# gnublin_ext_ssd1963.net
KiCad netlist of a schematic drawn in EAGLE
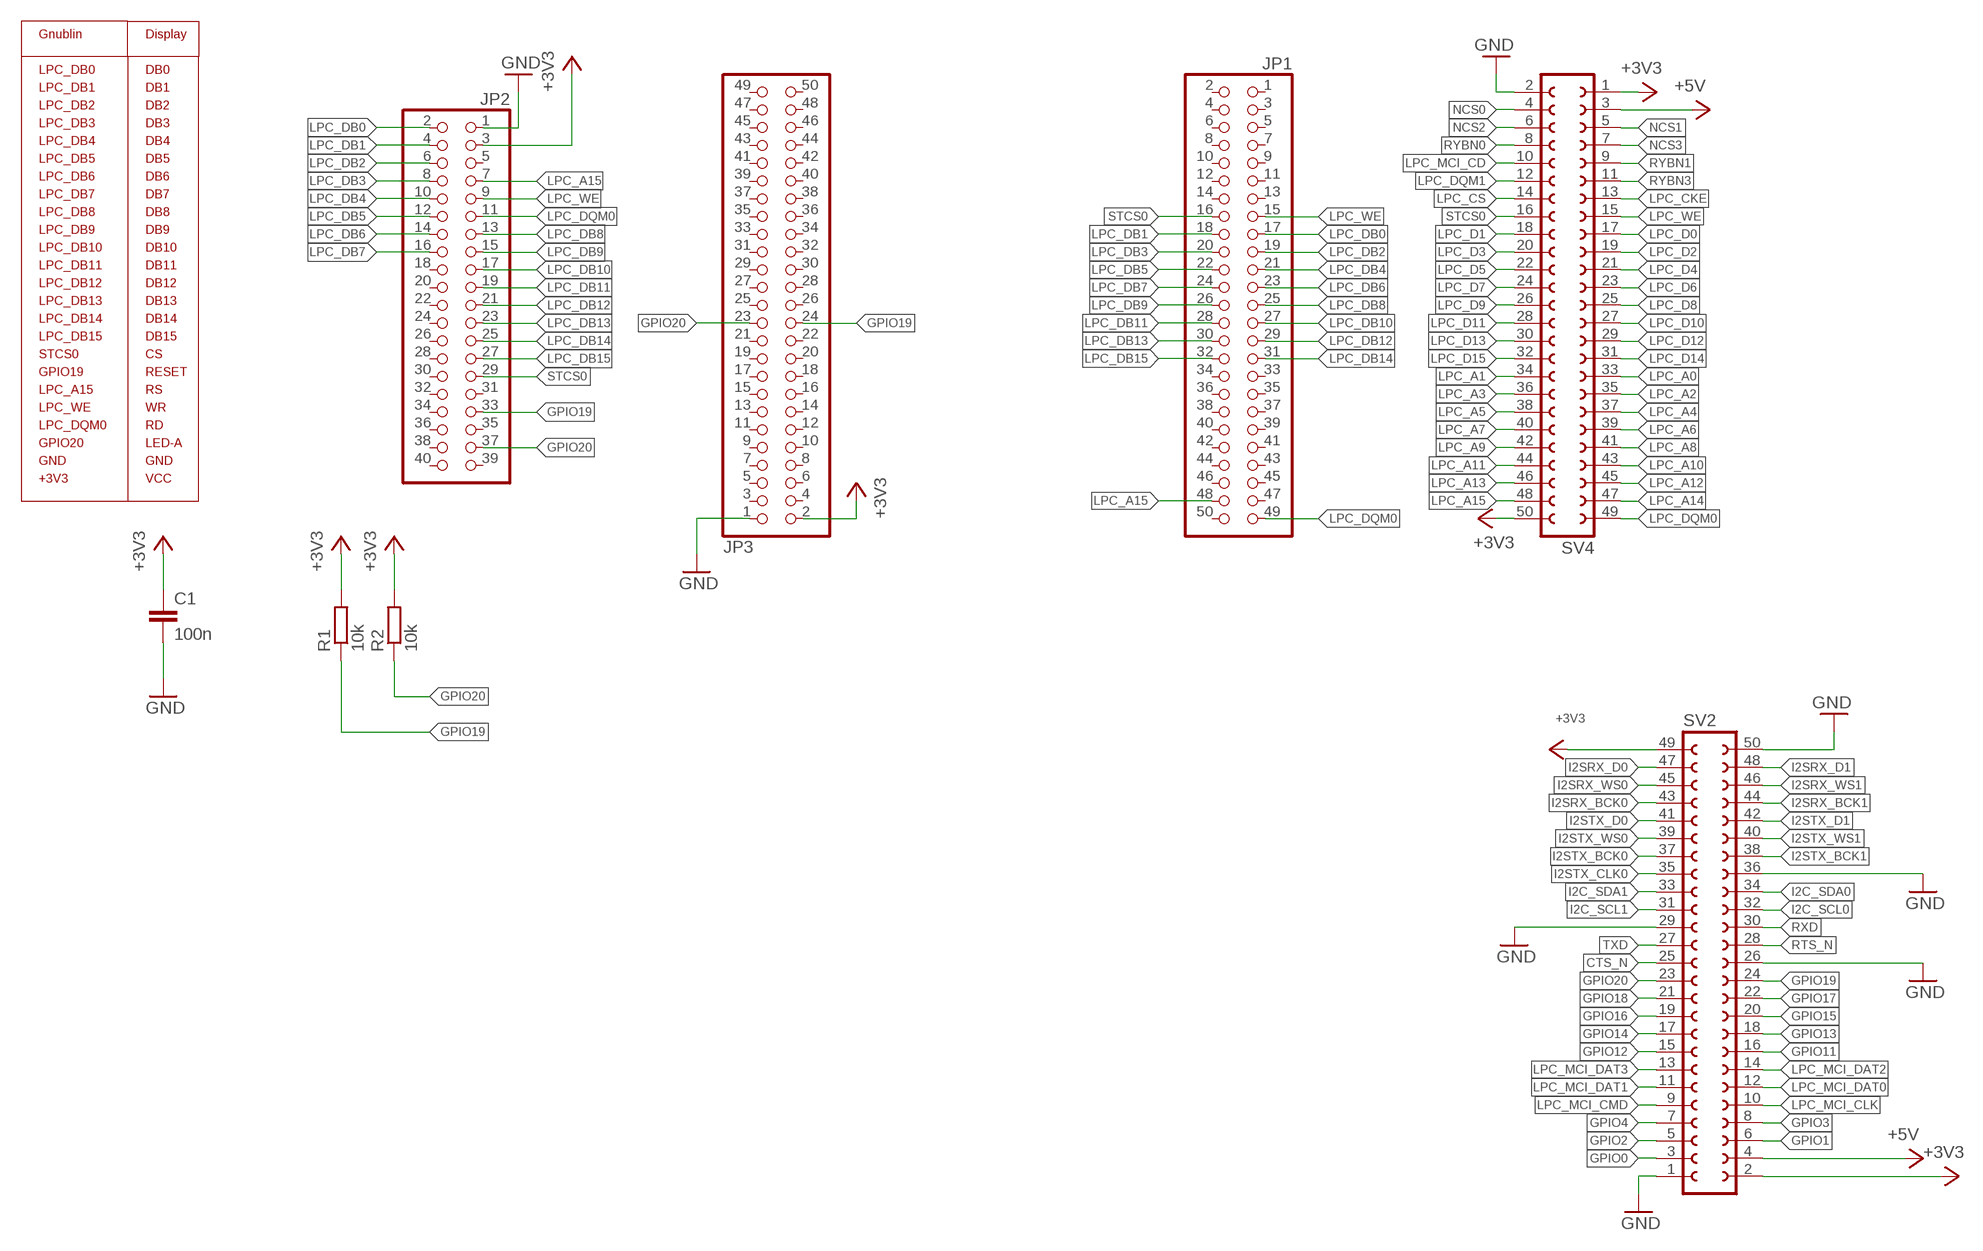
[diagram p0: schematic, sheet 1]

(export (version "E")
  (design (tool "Eeschema 10.0.6"))
  (components
    (comp (ref "C1")
      (value "100n")
      (footprint "eagle-import:C0805")
      (libsource (lib "eagle-import") (part "C-EUC0805"))
    )
    (comp (ref "JP1")
      (value "PINHD-2X25_2.54-SMD")
      (footprint "eagle-import:2X25SMD")
      (libsource (lib "eagle-import") (part "PINHD-2X25_2.54-SMD"))
    )
    (comp (ref "JP2")
      (value "PINHD-2X20")
      (footprint "eagle-import:2X20")
      (libsource (lib "eagle-import") (part "PINHD-2X20"))
    )
    (comp (ref "JP3")
      (value "PINHD-2X25_2.54-SMD")
      (footprint "eagle-import:2X25SMD")
      (libsource (lib "eagle-import") (part "PINHD-2X25_2.54-SMD"))
    )
    (comp (ref "R1")
      (value "10k")
      (footprint "eagle-import:R0603")
      (libsource (lib "eagle-import") (part "R-EU_R0603"))
    )
    (comp (ref "R2")
      (value "10k")
      (footprint "eagle-import:R0603")
      (libsource (lib "eagle-import") (part "R-EU_R0603"))
    )
    (comp (ref "SV2")
      (value "FE25-2")
      (footprint "eagle-import:FE25-2")
      (libsource (lib "eagle-import") (part "FE25-2"))
    )
    (comp (ref "SV4")
      (value "FE25-2")
      (footprint "eagle-import:FE25-2")
      (libsource (lib "eagle-import") (part "FE25-2"))
    )
  )
  (nets
    (net (code "1") (name "+3V3") (class "Default")
      (node (ref "C1") (pin "1") (pinfunction "1_1") (pintype "passive"))
      (node (ref "JP2") (pin "3") (pinfunction "3_3") (pintype "passive"))
      (node (ref "JP3") (pin "2") (pinfunction "2_2") (pintype "passive"))
      (node (ref "R1") (pin "2") (pinfunction "2_2") (pintype "passive"))
      (node (ref "R2") (pin "2") (pinfunction "2_2") (pintype "passive"))
      (node (ref "SV2") (pin "2") (pinfunction "2_2") (pintype "passive"))
      (node (ref "SV2") (pin "49") (pinfunction "49_49") (pintype "passive"))
      (node (ref "SV4") (pin "1") (pinfunction "1_1") (pintype "passive"))
      (node (ref "SV4") (pin "50") (pinfunction "50_50") (pintype "passive"))
    )
    (net (code "2") (name "+5V") (class "Default")
      (node (ref "SV2") (pin "4") (pinfunction "4_4") (pintype "passive"))
      (node (ref "SV4") (pin "3") (pinfunction "3_3") (pintype "passive"))
    )
    (net (code "3") (name "CTS_N") (class "Default")
      (node (ref "SV2") (pin "25") (pinfunction "25_25") (pintype "passive"))
    )
    (net (code "4") (name "GND") (class "Default")
      (node (ref "C1") (pin "2") (pinfunction "2_2") (pintype "passive"))
      (node (ref "JP2") (pin "1") (pinfunction "1_1") (pintype "passive"))
      (node (ref "JP3") (pin "1") (pinfunction "1_1") (pintype "passive"))
      (node (ref "SV2") (pin "1") (pinfunction "1_1") (pintype "passive"))
      (node (ref "SV2") (pin "26") (pinfunction "26_26") (pintype "passive"))
      (node (ref "SV2") (pin "29") (pinfunction "29_29") (pintype "passive"))
      (node (ref "SV2") (pin "36") (pinfunction "36_36") (pintype "passive"))
      (node (ref "SV2") (pin "50") (pinfunction "50_50") (pintype "passive"))
      (node (ref "SV4") (pin "2") (pinfunction "2_2") (pintype "passive"))
    )
    (net (code "5") (name "GPIO0") (class "Default")
      (node (ref "SV2") (pin "3") (pinfunction "3_3") (pintype "passive"))
    )
    (net (code "6") (name "GPIO1") (class "Default")
      (node (ref "SV2") (pin "6") (pinfunction "6_6") (pintype "passive"))
    )
    (net (code "7") (name "GPIO2") (class "Default")
      (node (ref "SV2") (pin "5") (pinfunction "5_5") (pintype "passive"))
    )
    (net (code "8") (name "GPIO3") (class "Default")
      (node (ref "SV2") (pin "8") (pinfunction "8_8") (pintype "passive"))
    )
    (net (code "9") (name "GPIO4") (class "Default")
      (node (ref "SV2") (pin "7") (pinfunction "7_7") (pintype "passive"))
    )
    (net (code "10") (name "GPIO11") (class "Default")
      (node (ref "SV2") (pin "16") (pinfunction "16_16") (pintype "passive"))
    )
    (net (code "11") (name "GPIO12") (class "Default")
      (node (ref "SV2") (pin "15") (pinfunction "15_15") (pintype "passive"))
    )
    (net (code "12") (name "GPIO13") (class "Default")
      (node (ref "SV2") (pin "18") (pinfunction "18_18") (pintype "passive"))
    )
    (net (code "13") (name "GPIO14") (class "Default")
      (node (ref "SV2") (pin "17") (pinfunction "17_17") (pintype "passive"))
    )
    (net (code "14") (name "GPIO15") (class "Default")
      (node (ref "SV2") (pin "20") (pinfunction "20_20") (pintype "passive"))
    )
    (net (code "15") (name "GPIO16") (class "Default")
      (node (ref "SV2") (pin "19") (pinfunction "19_19") (pintype "passive"))
    )
    (net (code "16") (name "GPIO17") (class "Default")
      (node (ref "SV2") (pin "22") (pinfunction "22_22") (pintype "passive"))
    )
    (net (code "17") (name "GPIO18") (class "Default")
      (node (ref "SV2") (pin "21") (pinfunction "21_21") (pintype "passive"))
    )
    (net (code "18") (name "GPIO19") (class "Default")
      (node (ref "JP2") (pin "33") (pinfunction "33_33") (pintype "passive"))
      (node (ref "JP3") (pin "24") (pinfunction "24_24") (pintype "passive"))
      (node (ref "R1") (pin "1") (pinfunction "1_1") (pintype "passive"))
      (node (ref "SV2") (pin "24") (pinfunction "24_24") (pintype "passive"))
    )
    (net (code "19") (name "GPIO20") (class "Default")
      (node (ref "JP2") (pin "37") (pinfunction "37_37") (pintype "passive"))
      (node (ref "JP3") (pin "23") (pinfunction "23_23") (pintype "passive"))
      (node (ref "R2") (pin "1") (pinfunction "1_1") (pintype "passive"))
      (node (ref "SV2") (pin "23") (pinfunction "23_23") (pintype "passive"))
    )
    (net (code "20") (name "I2C_SCL0") (class "Default")
      (node (ref "SV2") (pin "32") (pinfunction "32_32") (pintype "passive"))
    )
    (net (code "21") (name "I2C_SCL1") (class "Default")
      (node (ref "SV2") (pin "31") (pinfunction "31_31") (pintype "passive"))
    )
    (net (code "22") (name "I2C_SDA0") (class "Default")
      (node (ref "SV2") (pin "34") (pinfunction "34_34") (pintype "passive"))
    )
    (net (code "23") (name "I2C_SDA1") (class "Default")
      (node (ref "SV2") (pin "33") (pinfunction "33_33") (pintype "passive"))
    )
    (net (code "24") (name "I2SRX_BCK0") (class "Default")
      (node (ref "SV2") (pin "43") (pinfunction "43_43") (pintype "passive"))
    )
    (net (code "25") (name "I2SRX_BCK1") (class "Default")
      (node (ref "SV2") (pin "44") (pinfunction "44_44") (pintype "passive"))
    )
    (net (code "26") (name "I2SRX_D0") (class "Default")
      (node (ref "SV2") (pin "47") (pinfunction "47_47") (pintype "passive"))
    )
    (net (code "27") (name "I2SRX_D1") (class "Default")
      (node (ref "SV2") (pin "48") (pinfunction "48_48") (pintype "passive"))
    )
    (net (code "28") (name "I2SRX_WS0") (class "Default")
      (node (ref "SV2") (pin "45") (pinfunction "45_45") (pintype "passive"))
    )
    (net (code "29") (name "I2SRX_WS1") (class "Default")
      (node (ref "SV2") (pin "46") (pinfunction "46_46") (pintype "passive"))
    )
    (net (code "30") (name "I2STX_BCK0") (class "Default")
      (node (ref "SV2") (pin "37") (pinfunction "37_37") (pintype "passive"))
    )
    (net (code "31") (name "I2STX_BCK1") (class "Default")
      (node (ref "SV2") (pin "38") (pinfunction "38_38") (pintype "passive"))
    )
    (net (code "32") (name "I2STX_CLK0") (class "Default")
      (node (ref "SV2") (pin "35") (pinfunction "35_35") (pintype "passive"))
    )
    (net (code "33") (name "I2STX_D0") (class "Default")
      (node (ref "SV2") (pin "41") (pinfunction "41_41") (pintype "passive"))
    )
    (net (code "34") (name "I2STX_D1") (class "Default")
      (node (ref "SV2") (pin "42") (pinfunction "42_42") (pintype "passive"))
    )
    (net (code "35") (name "I2STX_WS0") (class "Default")
      (node (ref "SV2") (pin "39") (pinfunction "39_39") (pintype "passive"))
    )
    (net (code "36") (name "I2STX_WS1") (class "Default")
      (node (ref "SV2") (pin "40") (pinfunction "40_40") (pintype "passive"))
    )
    (net (code "37") (name "LPC_A0") (class "Default")
      (node (ref "SV4") (pin "33") (pinfunction "33_33") (pintype "passive"))
    )
    (net (code "38") (name "LPC_A1") (class "Default")
      (node (ref "SV4") (pin "34") (pinfunction "34_34") (pintype "passive"))
    )
    (net (code "39") (name "LPC_A2") (class "Default")
      (node (ref "SV4") (pin "35") (pinfunction "35_35") (pintype "passive"))
    )
    (net (code "40") (name "LPC_A3") (class "Default")
      (node (ref "SV4") (pin "36") (pinfunction "36_36") (pintype "passive"))
    )
    (net (code "41") (name "LPC_A4") (class "Default")
      (node (ref "SV4") (pin "37") (pinfunction "37_37") (pintype "passive"))
    )
    (net (code "42") (name "LPC_A5") (class "Default")
      (node (ref "SV4") (pin "38") (pinfunction "38_38") (pintype "passive"))
    )
    (net (code "43") (name "LPC_A6") (class "Default")
      (node (ref "SV4") (pin "39") (pinfunction "39_39") (pintype "passive"))
    )
    (net (code "44") (name "LPC_A7") (class "Default")
      (node (ref "SV4") (pin "40") (pinfunction "40_40") (pintype "passive"))
    )
    (net (code "45") (name "LPC_A8") (class "Default")
      (node (ref "SV4") (pin "41") (pinfunction "41_41") (pintype "passive"))
    )
    (net (code "46") (name "LPC_A9") (class "Default")
      (node (ref "SV4") (pin "42") (pinfunction "42_42") (pintype "passive"))
    )
    (net (code "47") (name "LPC_A10") (class "Default")
      (node (ref "SV4") (pin "43") (pinfunction "43_43") (pintype "passive"))
    )
    (net (code "48") (name "LPC_A11") (class "Default")
      (node (ref "SV4") (pin "44") (pinfunction "44_44") (pintype "passive"))
    )
    (net (code "49") (name "LPC_A12") (class "Default")
      (node (ref "SV4") (pin "45") (pinfunction "45_45") (pintype "passive"))
    )
    (net (code "50") (name "LPC_A13") (class "Default")
      (node (ref "SV4") (pin "46") (pinfunction "46_46") (pintype "passive"))
    )
    (net (code "51") (name "LPC_A14") (class "Default")
      (node (ref "SV4") (pin "47") (pinfunction "47_47") (pintype "passive"))
    )
    (net (code "52") (name "LPC_A15") (class "Default")
      (node (ref "JP1") (pin "48") (pinfunction "48_48") (pintype "passive"))
      (node (ref "JP2") (pin "7") (pinfunction "7_7") (pintype "passive"))
      (node (ref "SV4") (pin "48") (pinfunction "48_48") (pintype "passive"))
    )
    (net (code "53") (name "LPC_CKE") (class "Default")
      (node (ref "SV4") (pin "13") (pinfunction "13_13") (pintype "passive"))
    )
    (net (code "54") (name "LPC_CS") (class "Default")
      (node (ref "SV4") (pin "14") (pinfunction "14_14") (pintype "passive"))
    )
    (net (code "55") (name "LPC_D0") (class "Default")
      (node (ref "SV4") (pin "17") (pinfunction "17_17") (pintype "passive"))
    )
    (net (code "56") (name "LPC_D1") (class "Default")
      (node (ref "SV4") (pin "18") (pinfunction "18_18") (pintype "passive"))
    )
    (net (code "57") (name "LPC_D2") (class "Default")
      (node (ref "SV4") (pin "19") (pinfunction "19_19") (pintype "passive"))
    )
    (net (code "58") (name "LPC_D3") (class "Default")
      (node (ref "SV4") (pin "20") (pinfunction "20_20") (pintype "passive"))
    )
    (net (code "59") (name "LPC_D4") (class "Default")
      (node (ref "SV4") (pin "21") (pinfunction "21_21") (pintype "passive"))
    )
    (net (code "60") (name "LPC_D5") (class "Default")
      (node (ref "SV4") (pin "22") (pinfunction "22_22") (pintype "passive"))
    )
    (net (code "61") (name "LPC_D6") (class "Default")
      (node (ref "SV4") (pin "23") (pinfunction "23_23") (pintype "passive"))
    )
    (net (code "62") (name "LPC_D7") (class "Default")
      (node (ref "SV4") (pin "24") (pinfunction "24_24") (pintype "passive"))
    )
    (net (code "63") (name "LPC_D8") (class "Default")
      (node (ref "SV4") (pin "25") (pinfunction "25_25") (pintype "passive"))
    )
    (net (code "64") (name "LPC_D9") (class "Default")
      (node (ref "SV4") (pin "26") (pinfunction "26_26") (pintype "passive"))
    )
    (net (code "65") (name "LPC_D10") (class "Default")
      (node (ref "SV4") (pin "27") (pinfunction "27_27") (pintype "passive"))
    )
    (net (code "66") (name "LPC_D11") (class "Default")
      (node (ref "SV4") (pin "28") (pinfunction "28_28") (pintype "passive"))
    )
    (net (code "67") (name "LPC_D12") (class "Default")
      (node (ref "SV4") (pin "29") (pinfunction "29_29") (pintype "passive"))
    )
    (net (code "68") (name "LPC_D13") (class "Default")
      (node (ref "SV4") (pin "30") (pinfunction "30_30") (pintype "passive"))
    )
    (net (code "69") (name "LPC_D14") (class "Default")
      (node (ref "SV4") (pin "31") (pinfunction "31_31") (pintype "passive"))
    )
    (net (code "70") (name "LPC_D15") (class "Default")
      (node (ref "SV4") (pin "32") (pinfunction "32_32") (pintype "passive"))
    )
    (net (code "71") (name "LPC_DB0") (class "Default")
      (node (ref "JP1") (pin "17") (pinfunction "17_17") (pintype "passive"))
      (node (ref "JP2") (pin "2") (pinfunction "2_2") (pintype "passive"))
    )
    (net (code "72") (name "LPC_DB1") (class "Default")
      (node (ref "JP1") (pin "18") (pinfunction "18_18") (pintype "passive"))
      (node (ref "JP2") (pin "4") (pinfunction "4_4") (pintype "passive"))
    )
    (net (code "73") (name "LPC_DB2") (class "Default")
      (node (ref "JP1") (pin "19") (pinfunction "19_19") (pintype "passive"))
      (node (ref "JP2") (pin "6") (pinfunction "6_6") (pintype "passive"))
    )
    (net (code "74") (name "LPC_DB3") (class "Default")
      (node (ref "JP1") (pin "20") (pinfunction "20_20") (pintype "passive"))
      (node (ref "JP2") (pin "8") (pinfunction "8_8") (pintype "passive"))
    )
    (net (code "75") (name "LPC_DB4") (class "Default")
      (node (ref "JP1") (pin "21") (pinfunction "21_21") (pintype "passive"))
      (node (ref "JP2") (pin "10") (pinfunction "10_10") (pintype "passive"))
    )
    (net (code "76") (name "LPC_DB5") (class "Default")
      (node (ref "JP1") (pin "22") (pinfunction "22_22") (pintype "passive"))
      (node (ref "JP2") (pin "12") (pinfunction "12_12") (pintype "passive"))
    )
    (net (code "77") (name "LPC_DB6") (class "Default")
      (node (ref "JP1") (pin "23") (pinfunction "23_23") (pintype "passive"))
      (node (ref "JP2") (pin "14") (pinfunction "14_14") (pintype "passive"))
    )
    (net (code "78") (name "LPC_DB7") (class "Default")
      (node (ref "JP1") (pin "24") (pinfunction "24_24") (pintype "passive"))
      (node (ref "JP2") (pin "16") (pinfunction "16_16") (pintype "passive"))
    )
    (net (code "79") (name "LPC_DB8") (class "Default")
      (node (ref "JP1") (pin "25") (pinfunction "25_25") (pintype "passive"))
      (node (ref "JP2") (pin "13") (pinfunction "13_13") (pintype "passive"))
    )
    (net (code "80") (name "LPC_DB9") (class "Default")
      (node (ref "JP1") (pin "26") (pinfunction "26_26") (pintype "passive"))
      (node (ref "JP2") (pin "15") (pinfunction "15_15") (pintype "passive"))
    )
    (net (code "81") (name "LPC_DB10") (class "Default")
      (node (ref "JP1") (pin "27") (pinfunction "27_27") (pintype "passive"))
      (node (ref "JP2") (pin "17") (pinfunction "17_17") (pintype "passive"))
    )
    (net (code "82") (name "LPC_DB11") (class "Default")
      (node (ref "JP1") (pin "28") (pinfunction "28_28") (pintype "passive"))
      (node (ref "JP2") (pin "19") (pinfunction "19_19") (pintype "passive"))
    )
    (net (code "83") (name "LPC_DB12") (class "Default")
      (node (ref "JP1") (pin "29") (pinfunction "29_29") (pintype "passive"))
      (node (ref "JP2") (pin "21") (pinfunction "21_21") (pintype "passive"))
    )
    (net (code "84") (name "LPC_DB13") (class "Default")
      (node (ref "JP1") (pin "30") (pinfunction "30_30") (pintype "passive"))
      (node (ref "JP2") (pin "23") (pinfunction "23_23") (pintype "passive"))
    )
    (net (code "85") (name "LPC_DB14") (class "Default")
      (node (ref "JP1") (pin "31") (pinfunction "31_31") (pintype "passive"))
      (node (ref "JP2") (pin "25") (pinfunction "25_25") (pintype "passive"))
    )
    (net (code "86") (name "LPC_DB15") (class "Default")
      (node (ref "JP1") (pin "32") (pinfunction "32_32") (pintype "passive"))
      (node (ref "JP2") (pin "27") (pinfunction "27_27") (pintype "passive"))
    )
    (net (code "87") (name "LPC_DQM0") (class "Default")
      (node (ref "JP1") (pin "49") (pinfunction "49_49") (pintype "passive"))
      (node (ref "JP2") (pin "11") (pinfunction "11_11") (pintype "passive"))
      (node (ref "SV4") (pin "49") (pinfunction "49_49") (pintype "passive"))
    )
    (net (code "88") (name "LPC_DQM1") (class "Default")
      (node (ref "SV4") (pin "12") (pinfunction "12_12") (pintype "passive"))
    )
    (net (code "89") (name "LPC_MCI_CD") (class "Default")
      (node (ref "SV4") (pin "10") (pinfunction "10_10") (pintype "passive"))
    )
    (net (code "90") (name "LPC_MCI_CLK") (class "Default")
      (node (ref "SV2") (pin "10") (pinfunction "10_10") (pintype "passive"))
    )
    (net (code "91") (name "LPC_MCI_CMD") (class "Default")
      (node (ref "SV2") (pin "9") (pinfunction "9_9") (pintype "passive"))
    )
    (net (code "92") (name "LPC_MCI_DAT0") (class "Default")
      (node (ref "SV2") (pin "12") (pinfunction "12_12") (pintype "passive"))
    )
    (net (code "93") (name "LPC_MCI_DAT1") (class "Default")
      (node (ref "SV2") (pin "11") (pinfunction "11_11") (pintype "passive"))
    )
    (net (code "94") (name "LPC_MCI_DAT2") (class "Default")
      (node (ref "SV2") (pin "14") (pinfunction "14_14") (pintype "passive"))
    )
    (net (code "95") (name "LPC_MCI_DAT3") (class "Default")
      (node (ref "SV2") (pin "13") (pinfunction "13_13") (pintype "passive"))
    )
    (net (code "96") (name "LPC_WE") (class "Default")
      (node (ref "JP1") (pin "15") (pinfunction "15_15") (pintype "passive"))
      (node (ref "JP2") (pin "9") (pinfunction "9_9") (pintype "passive"))
      (node (ref "SV4") (pin "15") (pinfunction "15_15") (pintype "passive"))
    )
    (net (code "97") (name "NCS0") (class "Default")
      (node (ref "SV4") (pin "4") (pinfunction "4_4") (pintype "passive"))
    )
    (net (code "98") (name "NCS1") (class "Default")
      (node (ref "SV4") (pin "5") (pinfunction "5_5") (pintype "passive"))
    )
    (net (code "99") (name "NCS2") (class "Default")
      (node (ref "SV4") (pin "6") (pinfunction "6_6") (pintype "passive"))
    )
    (net (code "100") (name "NCS3") (class "Default")
      (node (ref "SV4") (pin "7") (pinfunction "7_7") (pintype "passive"))
    )
    (net (code "101") (name "RTS_N") (class "Default")
      (node (ref "SV2") (pin "28") (pinfunction "28_28") (pintype "passive"))
    )
    (net (code "102") (name "RXD") (class "Default")
      (node (ref "SV2") (pin "30") (pinfunction "30_30") (pintype "passive"))
    )
    (net (code "103") (name "RYBN0") (class "Default")
      (node (ref "SV4") (pin "8") (pinfunction "8_8") (pintype "passive"))
    )
    (net (code "104") (name "RYBN1") (class "Default")
      (node (ref "SV4") (pin "9") (pinfunction "9_9") (pintype "passive"))
    )
    (net (code "105") (name "RYBN3") (class "Default")
      (node (ref "SV4") (pin "11") (pinfunction "11_11") (pintype "passive"))
    )
    (net (code "106") (name "STCS0") (class "Default")
      (node (ref "JP1") (pin "16") (pinfunction "16_16") (pintype "passive"))
      (node (ref "JP2") (pin "29") (pinfunction "29_29") (pintype "passive"))
      (node (ref "SV4") (pin "16") (pinfunction "16_16") (pintype "passive"))
    )
    (net (code "107") (name "TXD") (class "Default")
      (node (ref "SV2") (pin "27") (pinfunction "27_27") (pintype "passive"))
    )
    (net (code "108") (name "unconnected-(JP1-Pad1)") (class "Default")
      (node (ref "JP1") (pin "1") (pinfunction "1_1") (pintype "passive"))
    )
    (net (code "109") (name "unconnected-(JP1-Pad2)") (class "Default")
      (node (ref "JP1") (pin "2") (pinfunction "2_2") (pintype "passive"))
    )
    (net (code "110") (name "unconnected-(JP1-Pad3)") (class "Default")
      (node (ref "JP1") (pin "3") (pinfunction "3_3") (pintype "passive"))
    )
    (net (code "111") (name "unconnected-(JP1-Pad4)") (class "Default")
      (node (ref "JP1") (pin "4") (pinfunction "4_4") (pintype "passive"))
    )
    (net (code "112") (name "unconnected-(JP1-Pad5)") (class "Default")
      (node (ref "JP1") (pin "5") (pinfunction "5_5") (pintype "passive"))
    )
    (net (code "113") (name "unconnected-(JP1-Pad6)") (class "Default")
      (node (ref "JP1") (pin "6") (pinfunction "6_6") (pintype "passive"))
    )
    (net (code "114") (name "unconnected-(JP1-Pad7)") (class "Default")
      (node (ref "JP1") (pin "7") (pinfunction "7_7") (pintype "passive"))
    )
    (net (code "115") (name "unconnected-(JP1-Pad8)") (class "Default")
      (node (ref "JP1") (pin "8") (pinfunction "8_8") (pintype "passive"))
    )
    (net (code "116") (name "unconnected-(JP1-Pad9)") (class "Default")
      (node (ref "JP1") (pin "9") (pinfunction "9_9") (pintype "passive"))
    )
    (net (code "117") (name "unconnected-(JP1-Pad10)") (class "Default")
      (node (ref "JP1") (pin "10") (pinfunction "10_10") (pintype "passive"))
    )
    (net (code "118") (name "unconnected-(JP1-Pad11)") (class "Default")
      (node (ref "JP1") (pin "11") (pinfunction "11_11") (pintype "passive"))
    )
    (net (code "119") (name "unconnected-(JP1-Pad12)") (class "Default")
      (node (ref "JP1") (pin "12") (pinfunction "12_12") (pintype "passive"))
    )
    (net (code "120") (name "unconnected-(JP1-Pad13)") (class "Default")
      (node (ref "JP1") (pin "13") (pinfunction "13_13") (pintype "passive"))
    )
    (net (code "121") (name "unconnected-(JP1-Pad14)") (class "Default")
      (node (ref "JP1") (pin "14") (pinfunction "14_14") (pintype "passive"))
    )
    (net (code "122") (name "unconnected-(JP1-Pad33)") (class "Default")
      (node (ref "JP1") (pin "33") (pinfunction "33_33") (pintype "passive"))
    )
    (net (code "123") (name "unconnected-(JP1-Pad34)") (class "Default")
      (node (ref "JP1") (pin "34") (pinfunction "34_34") (pintype "passive"))
    )
    (net (code "124") (name "unconnected-(JP1-Pad35)") (class "Default")
      (node (ref "JP1") (pin "35") (pinfunction "35_35") (pintype "passive"))
    )
    (net (code "125") (name "unconnected-(JP1-Pad36)") (class "Default")
      (node (ref "JP1") (pin "36") (pinfunction "36_36") (pintype "passive"))
    )
    (net (code "126") (name "unconnected-(JP1-Pad37)") (class "Default")
      (node (ref "JP1") (pin "37") (pinfunction "37_37") (pintype "passive"))
    )
    (net (code "127") (name "unconnected-(JP1-Pad38)") (class "Default")
      (node (ref "JP1") (pin "38") (pinfunction "38_38") (pintype "passive"))
    )
    (net (code "128") (name "unconnected-(JP1-Pad39)") (class "Default")
      (node (ref "JP1") (pin "39") (pinfunction "39_39") (pintype "passive"))
    )
    (net (code "129") (name "unconnected-(JP1-Pad40)") (class "Default")
      (node (ref "JP1") (pin "40") (pinfunction "40_40") (pintype "passive"))
    )
    (net (code "130") (name "unconnected-(JP1-Pad41)") (class "Default")
      (node (ref "JP1") (pin "41") (pinfunction "41_41") (pintype "passive"))
    )
    (net (code "131") (name "unconnected-(JP1-Pad42)") (class "Default")
      (node (ref "JP1") (pin "42") (pinfunction "42_42") (pintype "passive"))
    )
    (net (code "132") (name "unconnected-(JP1-Pad43)") (class "Default")
      (node (ref "JP1") (pin "43") (pinfunction "43_43") (pintype "passive"))
    )
    (net (code "133") (name "unconnected-(JP1-Pad44)") (class "Default")
      (node (ref "JP1") (pin "44") (pinfunction "44_44") (pintype "passive"))
    )
    (net (code "134") (name "unconnected-(JP1-Pad45)") (class "Default")
      (node (ref "JP1") (pin "45") (pinfunction "45_45") (pintype "passive"))
    )
    (net (code "135") (name "unconnected-(JP1-Pad46)") (class "Default")
      (node (ref "JP1") (pin "46") (pinfunction "46_46") (pintype "passive"))
    )
    (net (code "136") (name "unconnected-(JP1-Pad47)") (class "Default")
      (node (ref "JP1") (pin "47") (pinfunction "47_47") (pintype "passive"))
    )
    (net (code "137") (name "unconnected-(JP1-Pad50)") (class "Default")
      (node (ref "JP1") (pin "50") (pinfunction "50_50") (pintype "passive"))
    )
    (net (code "138") (name "unconnected-(JP2-Pad5)") (class "Default")
      (node (ref "JP2") (pin "5") (pinfunction "5_5") (pintype "passive"))
    )
    (net (code "139") (name "unconnected-(JP2-Pad18)") (class "Default")
      (node (ref "JP2") (pin "18") (pinfunction "18_18") (pintype "passive"))
    )
    (net (code "140") (name "unconnected-(JP2-Pad20)") (class "Default")
      (node (ref "JP2") (pin "20") (pinfunction "20_20") (pintype "passive"))
    )
    (net (code "141") (name "unconnected-(JP2-Pad22)") (class "Default")
      (node (ref "JP2") (pin "22") (pinfunction "22_22") (pintype "passive"))
    )
    (net (code "142") (name "unconnected-(JP2-Pad24)") (class "Default")
      (node (ref "JP2") (pin "24") (pinfunction "24_24") (pintype "passive"))
    )
    (net (code "143") (name "unconnected-(JP2-Pad26)") (class "Default")
      (node (ref "JP2") (pin "26") (pinfunction "26_26") (pintype "passive"))
    )
    (net (code "144") (name "unconnected-(JP2-Pad28)") (class "Default")
      (node (ref "JP2") (pin "28") (pinfunction "28_28") (pintype "passive"))
    )
    (net (code "145") (name "unconnected-(JP2-Pad30)") (class "Default")
      (node (ref "JP2") (pin "30") (pinfunction "30_30") (pintype "passive"))
    )
    (net (code "146") (name "unconnected-(JP2-Pad31)") (class "Default")
      (node (ref "JP2") (pin "31") (pinfunction "31_31") (pintype "passive"))
    )
    (net (code "147") (name "unconnected-(JP2-Pad32)") (class "Default")
      (node (ref "JP2") (pin "32") (pinfunction "32_32") (pintype "passive"))
    )
    (net (code "148") (name "unconnected-(JP2-Pad34)") (class "Default")
      (node (ref "JP2") (pin "34") (pinfunction "34_34") (pintype "passive"))
    )
    (net (code "149") (name "unconnected-(JP2-Pad35)") (class "Default")
      (node (ref "JP2") (pin "35") (pinfunction "35_35") (pintype "passive"))
    )
    (net (code "150") (name "unconnected-(JP2-Pad36)") (class "Default")
      (node (ref "JP2") (pin "36") (pinfunction "36_36") (pintype "passive"))
    )
    (net (code "151") (name "unconnected-(JP2-Pad38)") (class "Default")
      (node (ref "JP2") (pin "38") (pinfunction "38_38") (pintype "passive"))
    )
    (net (code "152") (name "unconnected-(JP2-Pad39)") (class "Default")
      (node (ref "JP2") (pin "39") (pinfunction "39_39") (pintype "passive"))
    )
    (net (code "153") (name "unconnected-(JP2-Pad40)") (class "Default")
      (node (ref "JP2") (pin "40") (pinfunction "40_40") (pintype "passive"))
    )
    (net (code "154") (name "unconnected-(JP3-Pad3)") (class "Default")
      (node (ref "JP3") (pin "3") (pinfunction "3_3") (pintype "passive"))
    )
    (net (code "155") (name "unconnected-(JP3-Pad4)") (class "Default")
      (node (ref "JP3") (pin "4") (pinfunction "4_4") (pintype "passive"))
    )
    (net (code "156") (name "unconnected-(JP3-Pad5)") (class "Default")
      (node (ref "JP3") (pin "5") (pinfunction "5_5") (pintype "passive"))
    )
    (net (code "157") (name "unconnected-(JP3-Pad6)") (class "Default")
      (node (ref "JP3") (pin "6") (pinfunction "6_6") (pintype "passive"))
    )
    (net (code "158") (name "unconnected-(JP3-Pad7)") (class "Default")
      (node (ref "JP3") (pin "7") (pinfunction "7_7") (pintype "passive"))
    )
    (net (code "159") (name "unconnected-(JP3-Pad8)") (class "Default")
      (node (ref "JP3") (pin "8") (pinfunction "8_8") (pintype "passive"))
    )
    (net (code "160") (name "unconnected-(JP3-Pad9)") (class "Default")
      (node (ref "JP3") (pin "9") (pinfunction "9_9") (pintype "passive"))
    )
    (net (code "161") (name "unconnected-(JP3-Pad10)") (class "Default")
      (node (ref "JP3") (pin "10") (pinfunction "10_10") (pintype "passive"))
    )
    (net (code "162") (name "unconnected-(JP3-Pad11)") (class "Default")
      (node (ref "JP3") (pin "11") (pinfunction "11_11") (pintype "passive"))
    )
    (net (code "163") (name "unconnected-(JP3-Pad12)") (class "Default")
      (node (ref "JP3") (pin "12") (pinfunction "12_12") (pintype "passive"))
    )
    (net (code "164") (name "unconnected-(JP3-Pad13)") (class "Default")
      (node (ref "JP3") (pin "13") (pinfunction "13_13") (pintype "passive"))
    )
    (net (code "165") (name "unconnected-(JP3-Pad14)") (class "Default")
      (node (ref "JP3") (pin "14") (pinfunction "14_14") (pintype "passive"))
    )
    (net (code "166") (name "unconnected-(JP3-Pad15)") (class "Default")
      (node (ref "JP3") (pin "15") (pinfunction "15_15") (pintype "passive"))
    )
    (net (code "167") (name "unconnected-(JP3-Pad16)") (class "Default")
      (node (ref "JP3") (pin "16") (pinfunction "16_16") (pintype "passive"))
    )
    (net (code "168") (name "unconnected-(JP3-Pad17)") (class "Default")
      (node (ref "JP3") (pin "17") (pinfunction "17_17") (pintype "passive"))
    )
    (net (code "169") (name "unconnected-(JP3-Pad18)") (class "Default")
      (node (ref "JP3") (pin "18") (pinfunction "18_18") (pintype "passive"))
    )
    (net (code "170") (name "unconnected-(JP3-Pad19)") (class "Default")
      (node (ref "JP3") (pin "19") (pinfunction "19_19") (pintype "passive"))
    )
    (net (code "171") (name "unconnected-(JP3-Pad20)") (class "Default")
      (node (ref "JP3") (pin "20") (pinfunction "20_20") (pintype "passive"))
    )
    (net (code "172") (name "unconnected-(JP3-Pad21)") (class "Default")
      (node (ref "JP3") (pin "21") (pinfunction "21_21") (pintype "passive"))
    )
    (net (code "173") (name "unconnected-(JP3-Pad22)") (class "Default")
      (node (ref "JP3") (pin "22") (pinfunction "22_22") (pintype "passive"))
    )
    (net (code "174") (name "unconnected-(JP3-Pad25)") (class "Default")
      (node (ref "JP3") (pin "25") (pinfunction "25_25") (pintype "passive"))
    )
    (net (code "175") (name "unconnected-(JP3-Pad26)") (class "Default")
      (node (ref "JP3") (pin "26") (pinfunction "26_26") (pintype "passive"))
    )
    (net (code "176") (name "unconnected-(JP3-Pad27)") (class "Default")
      (node (ref "JP3") (pin "27") (pinfunction "27_27") (pintype "passive"))
    )
    (net (code "177") (name "unconnected-(JP3-Pad28)") (class "Default")
      (node (ref "JP3") (pin "28") (pinfunction "28_28") (pintype "passive"))
    )
    (net (code "178") (name "unconnected-(JP3-Pad29)") (class "Default")
      (node (ref "JP3") (pin "29") (pinfunction "29_29") (pintype "passive"))
    )
    (net (code "179") (name "unconnected-(JP3-Pad30)") (class "Default")
      (node (ref "JP3") (pin "30") (pinfunction "30_30") (pintype "passive"))
    )
    (net (code "180") (name "unconnected-(JP3-Pad31)") (class "Default")
      (node (ref "JP3") (pin "31") (pinfunction "31_31") (pintype "passive"))
    )
    (net (code "181") (name "unconnected-(JP3-Pad32)") (class "Default")
      (node (ref "JP3") (pin "32") (pinfunction "32_32") (pintype "passive"))
    )
    (net (code "182") (name "unconnected-(JP3-Pad33)") (class "Default")
      (node (ref "JP3") (pin "33") (pinfunction "33_33") (pintype "passive"))
    )
    (net (code "183") (name "unconnected-(JP3-Pad34)") (class "Default")
      (node (ref "JP3") (pin "34") (pinfunction "34_34") (pintype "passive"))
    )
    (net (code "184") (name "unconnected-(JP3-Pad35)") (class "Default")
      (node (ref "JP3") (pin "35") (pinfunction "35_35") (pintype "passive"))
    )
    (net (code "185") (name "unconnected-(JP3-Pad36)") (class "Default")
      (node (ref "JP3") (pin "36") (pinfunction "36_36") (pintype "passive"))
    )
    (net (code "186") (name "unconnected-(JP3-Pad37)") (class "Default")
      (node (ref "JP3") (pin "37") (pinfunction "37_37") (pintype "passive"))
    )
    (net (code "187") (name "unconnected-(JP3-Pad38)") (class "Default")
      (node (ref "JP3") (pin "38") (pinfunction "38_38") (pintype "passive"))
    )
    (net (code "188") (name "unconnected-(JP3-Pad39)") (class "Default")
      (node (ref "JP3") (pin "39") (pinfunction "39_39") (pintype "passive"))
    )
    (net (code "189") (name "unconnected-(JP3-Pad40)") (class "Default")
      (node (ref "JP3") (pin "40") (pinfunction "40_40") (pintype "passive"))
    )
    (net (code "190") (name "unconnected-(JP3-Pad41)") (class "Default")
      (node (ref "JP3") (pin "41") (pinfunction "41_41") (pintype "passive"))
    )
    (net (code "191") (name "unconnected-(JP3-Pad42)") (class "Default")
      (node (ref "JP3") (pin "42") (pinfunction "42_42") (pintype "passive"))
    )
    (net (code "192") (name "unconnected-(JP3-Pad43)") (class "Default")
      (node (ref "JP3") (pin "43") (pinfunction "43_43") (pintype "passive"))
    )
    (net (code "193") (name "unconnected-(JP3-Pad44)") (class "Default")
      (node (ref "JP3") (pin "44") (pinfunction "44_44") (pintype "passive"))
    )
    (net (code "194") (name "unconnected-(JP3-Pad45)") (class "Default")
      (node (ref "JP3") (pin "45") (pinfunction "45_45") (pintype "passive"))
    )
    (net (code "195") (name "unconnected-(JP3-Pad46)") (class "Default")
      (node (ref "JP3") (pin "46") (pinfunction "46_46") (pintype "passive"))
    )
    (net (code "196") (name "unconnected-(JP3-Pad47)") (class "Default")
      (node (ref "JP3") (pin "47") (pinfunction "47_47") (pintype "passive"))
    )
    (net (code "197") (name "unconnected-(JP3-Pad48)") (class "Default")
      (node (ref "JP3") (pin "48") (pinfunction "48_48") (pintype "passive"))
    )
    (net (code "198") (name "unconnected-(JP3-Pad49)") (class "Default")
      (node (ref "JP3") (pin "49") (pinfunction "49_49") (pintype "passive"))
    )
    (net (code "199") (name "unconnected-(JP3-Pad50)") (class "Default")
      (node (ref "JP3") (pin "50") (pinfunction "50_50") (pintype "passive"))
    )
  )
)
